# MICROSD.net
KiCad netlist of a schematic drawn in Altium Designer
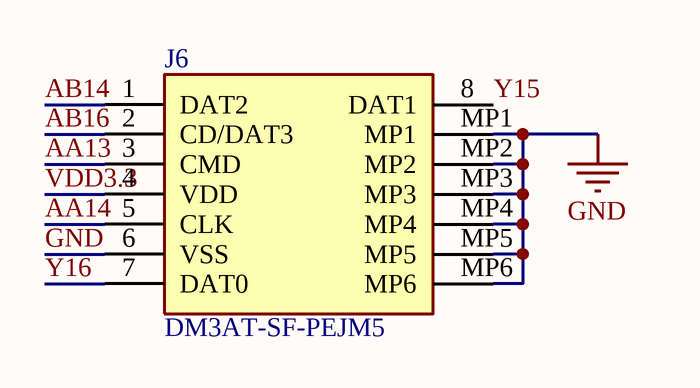
[diagram p0: MICROSD.SchDoc]

(export (version "E")
  (design (tool "Eeschema 10.0.6"))
  (components
    (comp (ref "J6")
      (value "DM3AT-SF-PEJM5")
      (footprint "SamacSys:DM3ATSFPEJM5")
      (description "Connector")
      (fields (field (name "MOUSER PART NUMBER") "798-DM3AT-SF-PEJM5"))
      (libsource (lib "*") (part "DM3AT-SF-PEJM5"))
    )
  )
  (nets
    (net (code "1") (name "/AA13") (class "Default")
      (node (ref "J6") (pin "3") (pinfunction "CMD_3") (pintype "passive"))
    )
    (net (code "2") (name "/AA14") (class "Default")
      (node (ref "J6") (pin "5") (pinfunction "CLK_5") (pintype "passive"))
    )
    (net (code "3") (name "/AB14") (class "Default")
      (node (ref "J6") (pin "1") (pinfunction "DAT2_1") (pintype "passive"))
    )
    (net (code "4") (name "/AB16") (class "Default")
      (node (ref "J6") (pin "2") (pinfunction "CD/DAT3_2") (pintype "passive"))
    )
    (net (code "5") (name "/VDD3.3") (class "Default")
      (node (ref "J6") (pin "4") (pinfunction "VDD_4") (pintype "passive"))
    )
    (net (code "6") (name "/Y15") (class "Default")
      (node (ref "J6") (pin "8") (pinfunction "DAT1_8") (pintype "passive"))
    )
    (net (code "7") (name "/Y16") (class "Default")
      (node (ref "J6") (pin "7") (pinfunction "DAT0_7") (pintype "passive"))
    )
    (net (code "8") (name "GND") (class "Default")
      (node (ref "J6") (pin "6") (pinfunction "VSS_6") (pintype "passive"))
      (node (ref "J6") (pin "MP1") (pinfunction "MP1_MP1") (pintype "passive"))
      (node (ref "J6") (pin "MP2") (pinfunction "MP2_MP2") (pintype "passive"))
      (node (ref "J6") (pin "MP3") (pinfunction "MP3_MP3") (pintype "passive"))
      (node (ref "J6") (pin "MP4") (pinfunction "MP4_MP4") (pintype "passive"))
      (node (ref "J6") (pin "MP5") (pinfunction "MP5_MP5") (pintype "passive"))
      (node (ref "J6") (pin "MP6") (pinfunction "MP6_MP6") (pintype "passive"))
    )
  )
)
